# Sheet1.net
KiCad netlist of a schematic drawn in Altium Designer
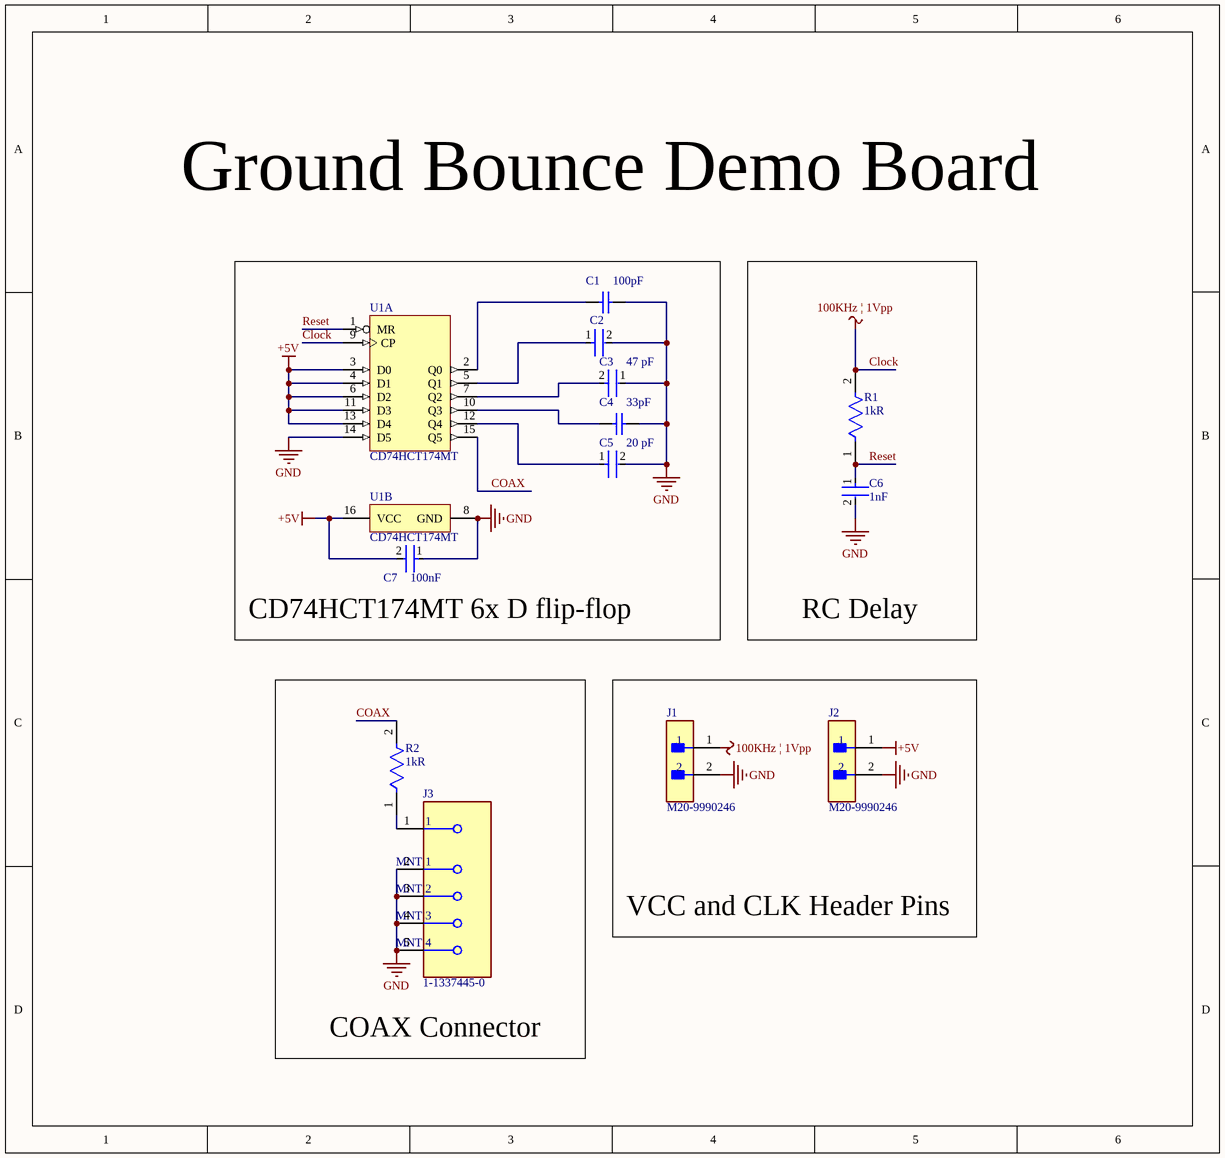
[diagram p0: Sheet1.SchDoc]

(export (version "E")
  (design (tool "Eeschema 10.0.6"))
  (components
    (comp (ref "C1")
      (value "0402YC101JAT2A")
      (footprint "CAPC1005X56X25NL10T15")
      (fields (field (name "MANUFACTURER") "AVX Interconnect / Elco") (field (name "PARAMETER 1") "100pF"))
      (libsource (lib "Altium Content Vault") (part "CAP"))
    )
    (comp (ref "C2")
      (value "CL05C750JB5NNNC")
      (footprint "FP-CL794-IPC_C")
      (description "Cap Ceramic 75pF 50V C0G ±5% SMD 0402 +125°C Paper T/R")
      (fields (field (name "TOLERANCE") "5%"))
      (libsource (lib "Altium Content Vault") (part "b4654b650e69147ec39a6b967a45e02"))
    )
    (comp (ref "C3")
      (value "47 pF")
      (footprint "FP-CBR04C-MFG")
      (description "CAP CER 47PF 25V C0G/NP0 0402")
      (fields
        (field (name "MANUFACTURER") "KEMET")
        (field (name "OCTOPART") "https://octopart.com/cbr04c470f3gac-kemet-30609232")
      )
      (libsource (lib "Altium Content Vault") (part "236180d848d6139a670b325ea6854c9"))
    )
    (comp (ref "C4")
      (value "C0402T330J3GACTU")
      (footprint "CAPC1005X55X30ML05T10")
      (fields (field (name "MANUFACTURER") "Kemet") (field (name "PARAMETER 1") "33pF"))
      (libsource (lib "Altium Content Vault") (part "CAP"))
    )
    (comp (ref "C5")
      (value "C0402C200J3GACTU")
      (footprint "FP-C0402-BB-MFG")
      (description "CAP CER 20PF 25V NP0 0402")
      (fields
        (field (name "CAPACITANCE") "20 pF")
        (field (name "OCTOPART") "https://octopart.com/c0402c200j3gactu-kemet-14400860")
        (field (name "TOLERANCE") "0.05")
      )
      (libsource (lib "Altium Content Vault") (part "b4654b650e69147ec39a6b967a45e02"))
    )
    (comp (ref "C6")
      (value "C1005X7R1V104K050BB")
      (footprint "FP-C1005-050-0_05-IPC_C")
      (description "Multilayer Ceramic Capacitors 100nF ±10% 35V X7R SMD 0402")
      (fields
        (field (name "VOLTAGE") "35V")
        (field (name "CAPACITANCE") "1nF")
        (field (name "TOLERANCE") "10%")
      )
      (libsource (lib "Altium Content Vault") (part "b4654b650e69147ec39a6b967a45e02"))
    )
    (comp (ref "C7")
      (value "C1005X7R1V104K050BB")
      (footprint "FP-C1005-050-0_05-IPC_C")
      (description "Multilayer Ceramic Capacitors 100nF ±10% 35V X7R SMD 0402")
      (fields
        (field (name "VOLTAGE") "35V")
        (field (name "CAPACITANCE") "100nF")
        (field (name "TOLERANCE") "10%")
      )
      (libsource (lib "Altium Content Vault") (part "b4654b650e69147ec39a6b967a45e02"))
    )
    (comp (ref "J1")
      (value "M20-9990246")
      (footprint "FP-M20-9990246-MFG")
      (description "CONN HEADER VERT 2POS 2.54MM")
      (fields
        (field (name "OCTOPART") "https://octopart.com/m20-9990246-harwin-2590635")
        (field (name "MANUFACTURER") "Harwin")
      )
      (libsource (lib "Altium Content Vault") (part "3bc925449376181038e59eaffc5286c"))
    )
    (comp (ref "J2")
      (value "M20-9990246")
      (footprint "FP-M20-9990246-MFG")
      (description "CONN HEADER VERT 2POS 2.54MM")
      (fields
        (field (name "OCTOPART") "https://octopart.com/m20-9990246-harwin-2590635")
        (field (name "MANUFACTURER") "Harwin")
      )
      (libsource (lib "Altium Content Vault") (part "3bc925449376181038e59eaffc5286c"))
    )
    (comp (ref "J3")
      (value "1-1337445-0")
      (footprint "FP-1-1337445-0-MFG")
      (description "CONN BNC JACK STR 50 OHM PCB")
      (libsource (lib "Altium Content Vault") (part "c65b8a639cdaef1819ea20b5466f8fa"))
    )
    (comp (ref "R1")
      (value "MCS0402MD1002BE100")
      (footprint "FP-MCS0402-IPC_B")
      (description "RES SMD 1.2K OHM 1% 1/10W 0402")
      (fields (field (name "TOLERANCE") "0.1%") (field (name "RESISTANCE") "1kR"))
      (libsource (lib "Altium Content Vault") (part "1029c3af85768c4190bb7ad29bc67b5"))
    )
    (comp (ref "R2")
      (value "RC1005F102CS")
      (footprint "FP-RC1005-IPC_A")
      (description "Res Thick Film 0402 1kΩ 1% 0.063W ±100ppm/°C Molded SMD T/R")
      (fields (field (name "RESISTANCE") "1kR") (field (name "TOLERANCE") "1%"))
      (libsource (lib "Altium Content Vault") (part "1029c3af85768c4190bb7ad29bc67b5"))
    )
    (comp (ref "U1")
      (value "CD74HCT174MT")
      (footprint "D0016A_L")
      (description "High Speed CMOS Logic Hex D-Type Flip-Flop with Reset, D0016A, SMALL T&R")
      (fields
        (field (name "GENERIC PART NUMBER") "CD74HCT174")
        (field (name "MANUFACTURER") "Texas Instruments")
      )
      (libsource (lib "Altium Content Vault") (part "TI-CDX4HCX174-16"))
    )
  )
  (nets
    (net (code "1") (name "+5V") (class "Default")
      (node (ref "C7") (pin "2") (pinfunction "2_2") (pintype "passive"))
      (node (ref "J2") (pin "1") (pinfunction "1_1") (pintype "passive"))
      (node (ref "U1") (pin "11") (pinfunction "D3_11") (pintype "input"))
      (node (ref "U1") (pin "13") (pinfunction "D4_13") (pintype "input"))
      (node (ref "U1") (pin "16") (pinfunction "VCC_16") (pintype "power_in"))
      (node (ref "U1") (pin "3") (pinfunction "D0_3") (pintype "input"))
      (node (ref "U1") (pin "4") (pinfunction "D1_4") (pintype "input"))
      (node (ref "U1") (pin "6") (pinfunction "D2_6") (pintype "input"))
    )
    (net (code "2") (name "/COAX") (class "Default")
      (node (ref "R2") (pin "2") (pinfunction "2_2") (pintype "passive"))
      (node (ref "U1") (pin "15") (pinfunction "Q5_15") (pintype "output"))
    )
    (net (code "3") (name "/Reset") (class "Default")
      (node (ref "C6") (pin "1") (pinfunction "1_1") (pintype "passive"))
      (node (ref "R1") (pin "1") (pinfunction "1_1") (pintype "passive"))
      (node (ref "U1") (pin "1") (pinfunction "MR_1") (pintype "input"))
    )
    (net (code "4") (name "100KHz ¦ 1Vpp") (class "Default")
      (node (ref "J1") (pin "1") (pinfunction "1_1") (pintype "passive"))
      (node (ref "R1") (pin "2") (pinfunction "2_2") (pintype "passive"))
      (node (ref "U1") (pin "9") (pinfunction "CP_9") (pintype "input"))
    )
    (net (code "5") (name "GND") (class "Default")
      (node (ref "C1") (pin "2") (pinfunction "2_2") (pintype "passive"))
      (node (ref "C2") (pin "2") (pinfunction "2_2") (pintype "passive"))
      (node (ref "C3") (pin "1") (pinfunction "1_1") (pintype "passive"))
      (node (ref "C4") (pin "2") (pinfunction "2_2") (pintype "passive"))
      (node (ref "C5") (pin "2") (pinfunction "2_2") (pintype "passive"))
      (node (ref "C6") (pin "2") (pinfunction "2_2") (pintype "passive"))
      (node (ref "C7") (pin "1") (pinfunction "1_1") (pintype "passive"))
      (node (ref "J1") (pin "2") (pinfunction "2_2") (pintype "passive"))
      (node (ref "J2") (pin "2") (pinfunction "2_2") (pintype "passive"))
      (node (ref "J3") (pin "2") (pinfunction "MNT_1_2") (pintype "passive"))
      (node (ref "J3") (pin "3") (pinfunction "MNT_2_3") (pintype "passive"))
      (node (ref "J3") (pin "4") (pinfunction "MNT_3_4") (pintype "passive"))
      (node (ref "J3") (pin "5") (pinfunction "MNT_4_5") (pintype "passive"))
      (node (ref "U1") (pin "14") (pinfunction "D5_14") (pintype "input"))
      (node (ref "U1") (pin "8") (pinfunction "GND_8") (pintype "power_in"))
    )
    (net (code "6") (name "Net-(J3-Pad1)") (class "Default")
      (node (ref "J3") (pin "1") (pinfunction "1_1") (pintype "passive"))
      (node (ref "R2") (pin "1") (pinfunction "1_1") (pintype "passive"))
    )
    (net (code "7") (name "Net-(U1A-Q0)") (class "Default")
      (node (ref "C1") (pin "1") (pinfunction "1_1") (pintype "passive"))
      (node (ref "U1") (pin "2") (pinfunction "Q0_2") (pintype "output"))
    )
    (net (code "8") (name "Net-(U1A-Q1)") (class "Default")
      (node (ref "C2") (pin "1") (pinfunction "1_1") (pintype "passive"))
      (node (ref "U1") (pin "5") (pinfunction "Q1_5") (pintype "output"))
    )
    (net (code "9") (name "Net-(U1A-Q2)") (class "Default")
      (node (ref "C3") (pin "2") (pinfunction "2_2") (pintype "passive"))
      (node (ref "U1") (pin "7") (pinfunction "Q2_7") (pintype "output"))
    )
    (net (code "10") (name "Net-(U1A-Q3)") (class "Default")
      (node (ref "C4") (pin "1") (pinfunction "1_1") (pintype "passive"))
      (node (ref "U1") (pin "10") (pinfunction "Q3_10") (pintype "output"))
    )
    (net (code "11") (name "Net-(U1A-Q4)") (class "Default")
      (node (ref "C5") (pin "1") (pinfunction "1_1") (pintype "passive"))
      (node (ref "U1") (pin "12") (pinfunction "Q4_12") (pintype "output"))
    )
  )
)
